# Pinball10.net
KiCad netlist of a schematic drawn in EAGLE
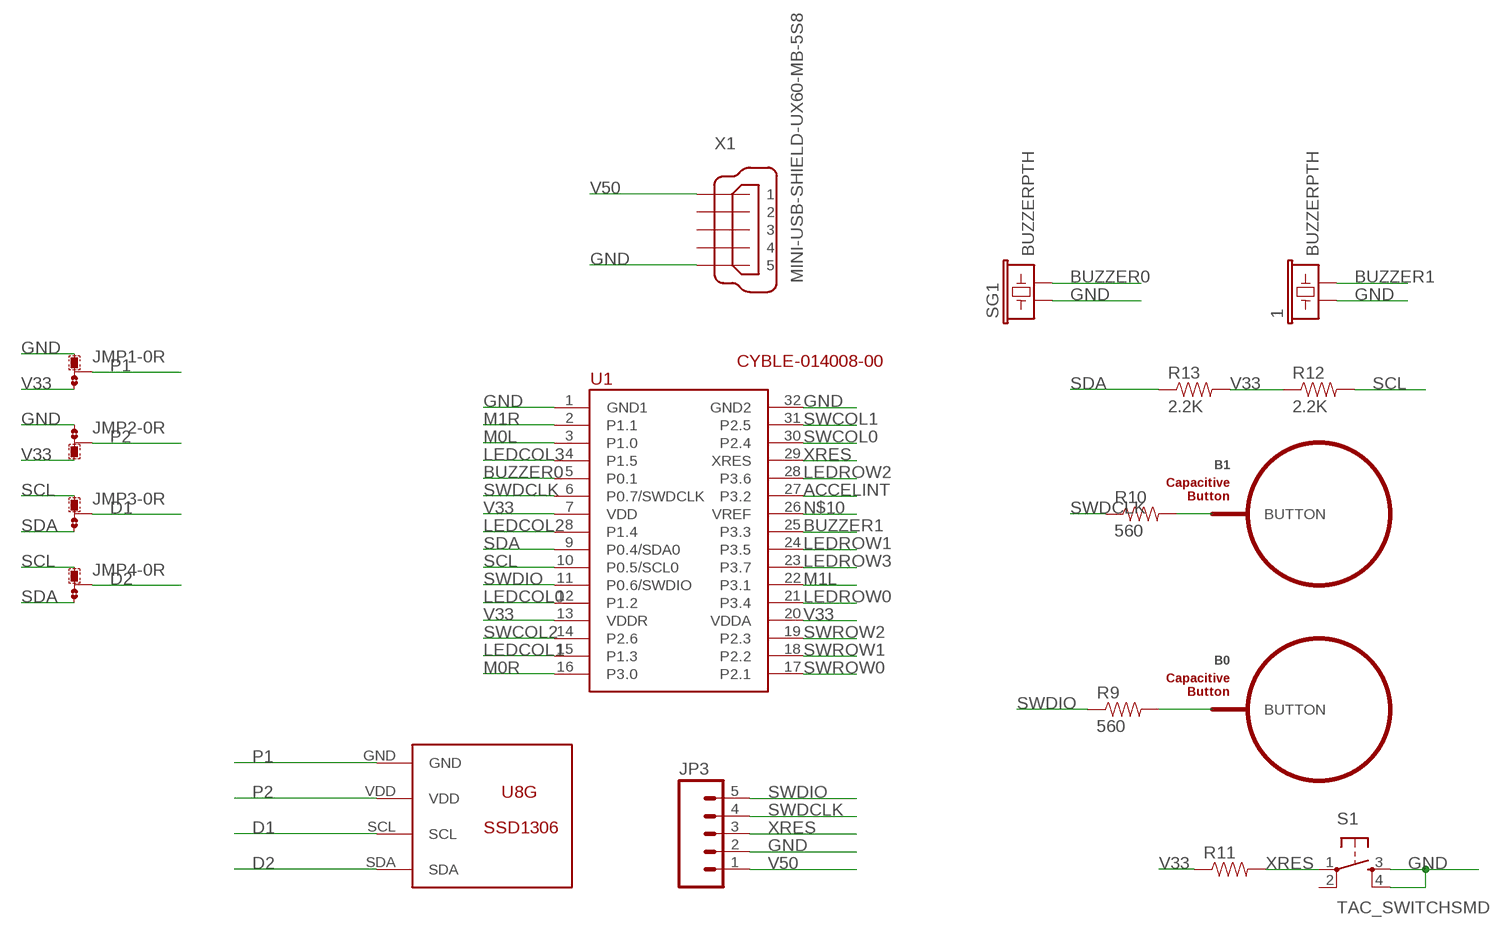
[diagram p0: schematic, sheet 1]
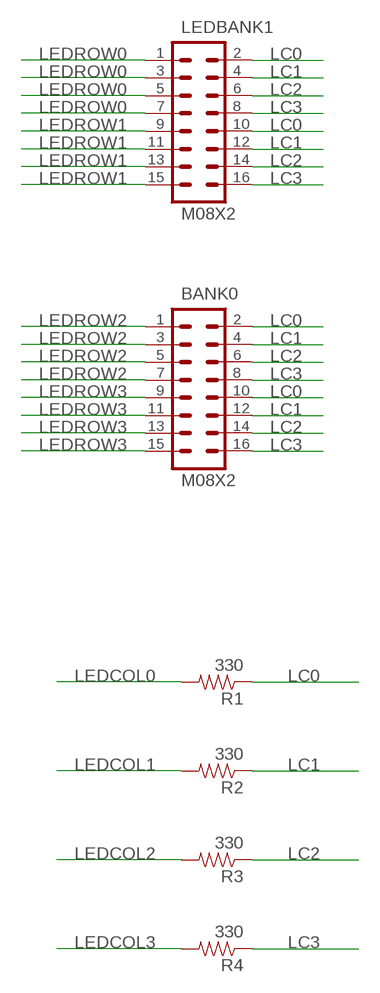
[diagram p1: schematic, sheet 2]
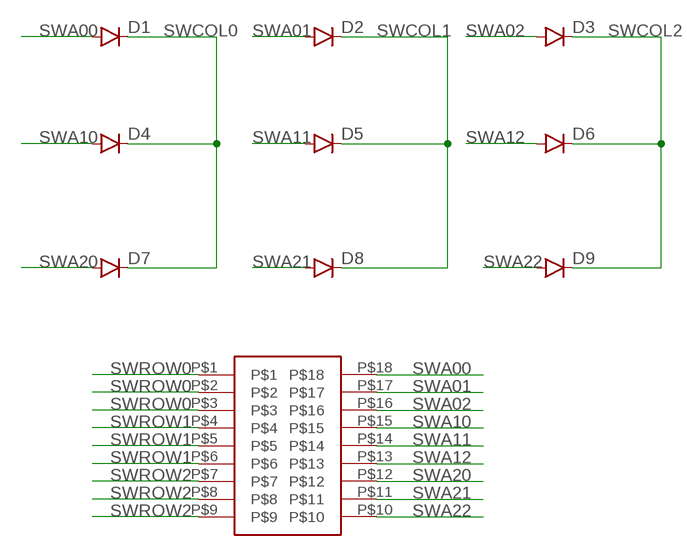
[diagram p2: schematic, sheet 3]
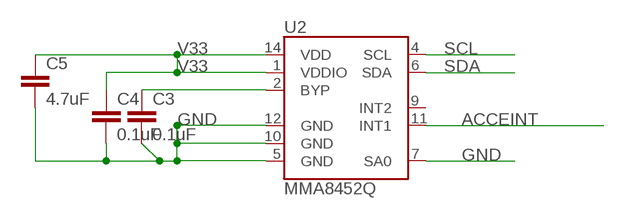
[diagram p3: schematic, sheet 4]
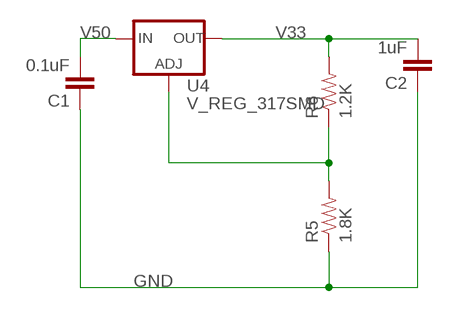
[diagram p4: schematic, sheet 5]
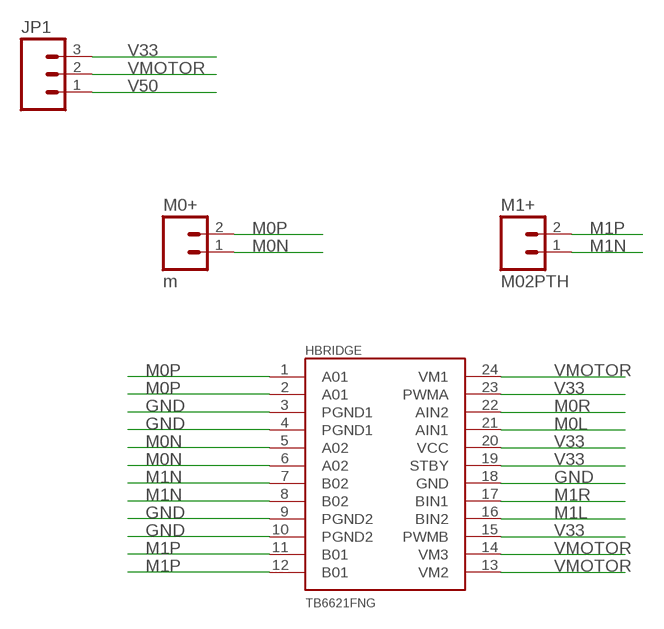
[diagram p5: schematic, sheet 6]
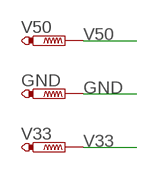
[diagram p6: schematic, sheet 7]

(export (version "E")
  (design (tool "Eeschema 10.0.6"))
  (components
    (comp (ref "GND")
      (value "GND")
      (footprint "eagle-import:P1-13")
      (libsource (lib "eagle-import") (part "PTR1PAD1-13"))
    )
    (comp (ref "V33")
      (value "PTR1PAD1-13")
      (footprint "eagle-import:P1-13")
      (libsource (lib "eagle-import") (part "PTR1PAD1-13"))
    )
    (comp (ref "V50")
      (value "PTR1PAD1-13")
      (footprint "eagle-import:P1-13")
      (libsource (lib "eagle-import") (part "PTR1PAD1-13"))
    )
    (comp (ref "D1")
      (value "DIODESOD")
      (footprint "eagle-import:SOD-323")
      (libsource (lib "eagle-import") (part "DIODESOD"))
    )
    (comp (ref "D2")
      (value "DIODESOD")
      (footprint "eagle-import:SOD-323")
      (libsource (lib "eagle-import") (part "DIODESOD"))
    )
    (comp (ref "D3")
      (value "DIODESOD")
      (footprint "eagle-import:SOD-323")
      (libsource (lib "eagle-import") (part "DIODESOD"))
    )
    (comp (ref "D4")
      (value "DIODESOD")
      (footprint "eagle-import:SOD-323")
      (libsource (lib "eagle-import") (part "DIODESOD"))
    )
    (comp (ref "D5")
      (value "DIODESOD")
      (footprint "eagle-import:SOD-323")
      (libsource (lib "eagle-import") (part "DIODESOD"))
    )
    (comp (ref "D6")
      (value "DIODESOD")
      (footprint "eagle-import:SOD-323")
      (libsource (lib "eagle-import") (part "DIODESOD"))
    )
    (comp (ref "D7")
      (value "DIODESOD")
      (footprint "eagle-import:SOD-323")
      (libsource (lib "eagle-import") (part "DIODESOD"))
    )
    (comp (ref "D8")
      (value "DIODESOD")
      (footprint "eagle-import:SOD-323")
      (libsource (lib "eagle-import") (part "DIODESOD"))
    )
    (comp (ref "D9")
      (value "DIODESOD")
      (footprint "eagle-import:SOD-323")
      (libsource (lib "eagle-import") (part "DIODESOD"))
    )
    (comp (ref "U$1")
      (value "9X2")
      (footprint "eagle-import:9X2")
      (libsource (lib "eagle-import") (part "9X2"))
    )
    (comp (ref "1")
      (value "BUZZERPTH")
      (footprint "eagle-import:BUZZER-12MM")
      (libsource (lib "eagle-import") (part "BUZZERPTH"))
    )
    (comp (ref "B0")
      (value "BUTTON_PASSIVE12MM")
      (footprint "eagle-import:BUTTON_PASSIVE_12MM")
      (libsource (lib "eagle-import") (part "BUTTON_PASSIVE12MM"))
    )
    (comp (ref "B1")
      (value "BUTTON_PASSIVE12MM")
      (footprint "eagle-import:BUTTON_PASSIVE_12MM")
      (libsource (lib "eagle-import") (part "BUTTON_PASSIVE12MM"))
    )
    (comp (ref "JMP1")
      (value "0R-JUMPB")
      (footprint "eagle-import:B0R-JMP")
      (libsource (lib "eagle-import") (part "0R-JUMPB"))
    )
    (comp (ref "JMP2")
      (value "0R-JUMPB")
      (footprint "eagle-import:B0R-JMP")
      (libsource (lib "eagle-import") (part "0R-JUMPB"))
    )
    (comp (ref "JMP3")
      (value "0R-JUMPB")
      (footprint "eagle-import:B0R-JMP")
      (libsource (lib "eagle-import") (part "0R-JUMPB"))
    )
    (comp (ref "JMP4")
      (value "0R-JUMPB")
      (footprint "eagle-import:B0R-JMP")
      (libsource (lib "eagle-import") (part "0R-JUMPB"))
    )
    (comp (ref "JP3")
      (value "M05LOCK")
      (footprint "eagle-import:1X05_LOCK")
      (libsource (lib "eagle-import") (part "M05LOCK"))
    )
    (comp (ref "R9")
      (value "560")
      (footprint "eagle-import:0805")
      (libsource (lib "eagle-import") (part "RESISTOR0805-RES"))
    )
    (comp (ref "R10")
      (value "560")
      (footprint "eagle-import:0805")
      (libsource (lib "eagle-import") (part "RESISTOR0805-RES"))
    )
    (comp (ref "R11")
      (value "RESISTOR0805-RES")
      (footprint "eagle-import:0805")
      (libsource (lib "eagle-import") (part "SparkFun-Resistors_RESISTOR0805-RES"))
    )
    (comp (ref "R12")
      (value "2.2K")
      (footprint "eagle-import:0805")
      (libsource (lib "eagle-import") (part "RESISTOR0805-RES"))
    )
    (comp (ref "R13")
      (value "2.2K")
      (footprint "eagle-import:0805")
      (libsource (lib "eagle-import") (part "RESISTOR0805-RES"))
    )
    (comp (ref "S1")
      (value "TAC_SWITCHSMD")
      (footprint "eagle-import:TACTILE-SWITCH-SMD")
      (libsource (lib "eagle-import") (part "TAC_SWITCHSMD"))
    )
    (comp (ref "SG1")
      (value "BUZZERPTH")
      (footprint "eagle-import:BUZZER-12MM")
      (libsource (lib "eagle-import") (part "BUZZERPTH"))
    )
    (comp (ref "U$2")
      (value "U8G-096-OLED")
      (footprint "eagle-import:096-SSD1306")
      (libsource (lib "eagle-import") (part "U8G-096-OLED"))
    )
    (comp (ref "U1")
      (value "CYBLE-014008-00")
      (footprint "eagle-import:PSOC-BLE-11MM-32")
      (libsource (lib "eagle-import") (part "CYBLE-014008-00"))
    )
    (comp (ref "X1")
      (value "MINI-USB-SHIELD-UX60-MB-5S8")
      (footprint "eagle-import:UX60-MB-5S8")
      (libsource (lib "eagle-import") (part "MINI-USB-SHIELD-UX60-MB-5S8"))
    )
    (comp (ref "C3")
      (value "0.1uF")
      (footprint "eagle-import:0805")
      (libsource (lib "eagle-import") (part "CAP0805"))
    )
    (comp (ref "C4")
      (value "0.1uF")
      (footprint "eagle-import:0805")
      (libsource (lib "eagle-import") (part "CAP0805"))
    )
    (comp (ref "C5")
      (value "4.7uF")
      (footprint "eagle-import:0805")
      (libsource (lib "eagle-import") (part "CAP0805"))
    )
    (comp (ref "U2")
      (value "MMA8452Q")
      (footprint "eagle-import:QFN-16_0.5MM")
      (libsource (lib "eagle-import") (part "MMA8452Q"))
    )
    (comp (ref "C1")
      (value "0.1uF")
      (footprint "eagle-import:0805")
      (libsource (lib "eagle-import") (part "CAP0805"))
    )
    (comp (ref "C2")
      (value "1uF")
      (footprint "eagle-import:0805")
      (libsource (lib "eagle-import") (part "CAP0805"))
    )
    (comp (ref "R5")
      (value "1.8K")
      (footprint "eagle-import:0805")
      (libsource (lib "eagle-import") (part "RESISTOR0805-RES"))
    )
    (comp (ref "R6")
      (value "1.2K")
      (footprint "eagle-import:0805")
      (libsource (lib "eagle-import") (part "RESISTOR0805-RES"))
    )
    (comp (ref "U4")
      (value "V_REG_317SMD")
      (footprint "eagle-import:SOT223")
      (libsource (lib "eagle-import") (part "V_REG_317SMD"))
    )
    (comp (ref "BANK0")
      (value "M08X2")
      (footprint "eagle-import:2X8")
      (libsource (lib "eagle-import") (part "M08X2"))
    )
    (comp (ref "LEDBANK1")
      (value "M08X2")
      (footprint "eagle-import:2X8")
      (libsource (lib "eagle-import") (part "M08X2"))
    )
    (comp (ref "R1")
      (value "330")
      (footprint "eagle-import:0805")
      (libsource (lib "eagle-import") (part "RESISTOR"))
    )
    (comp (ref "R2")
      (value "330")
      (footprint "eagle-import:0805")
      (libsource (lib "eagle-import") (part "RESISTOR"))
    )
    (comp (ref "R3")
      (value "330")
      (footprint "eagle-import:0805")
      (libsource (lib "eagle-import") (part "RESISTOR"))
    )
    (comp (ref "R4")
      (value "330")
      (footprint "eagle-import:0805")
      (libsource (lib "eagle-import") (part "RESISTOR"))
    )
    (comp (ref "HBRIDGE")
      (value "TB6621FNG")
      (footprint "eagle-import:SSOP24")
      (libsource (lib "eagle-import") (part "TB6621FNG"))
    )
    (comp (ref "JP1")
      (value "M03PTH")
      (footprint "eagle-import:1X03")
      (libsource (lib "eagle-import") (part "M03PTH"))
    )
    (comp (ref "M0+")
      (value "m")
      (footprint "eagle-import:1X02")
      (libsource (lib "eagle-import") (part "M02PTH"))
    )
    (comp (ref "M1+")
      (value "M02PTH")
      (footprint "eagle-import:1X02")
      (libsource (lib "eagle-import") (part "M02PTH"))
    )
  )
  (nets
    (net (code "1") (name "ACCEINT") (class "Default")
      (node (ref "U2") (pin "11") (pinfunction "INT1_11") (pintype "bidirectional"))
    )
    (net (code "2") (name "ACCELINT") (class "Default")
      (node (ref "U1") (pin "27") (pinfunction "P3.2_27") (pintype "bidirectional"))
    )
    (net (code "3") (name "BUZZER0") (class "Default")
      (node (ref "SG1") (pin "-") (pinfunction "2_-") (pintype "passive"))
      (node (ref "U1") (pin "5") (pinfunction "P0.1_5") (pintype "bidirectional"))
    )
    (net (code "4") (name "BUZZER1") (class "Default")
      (node (ref "1") (pin "-") (pinfunction "2_-") (pintype "passive"))
      (node (ref "U1") (pin "25") (pinfunction "P3.3_25") (pintype "bidirectional"))
    )
    (net (code "5") (name "D1") (class "Default")
      (node (ref "JMP3") (pin "2") (pinfunction "2_2") (pintype "passive"))
      (node (ref "U$2") (pin "SCL") (pinfunction "SCL_SCL") (pintype "bidirectional"))
    )
    (net (code "6") (name "D2") (class "Default")
      (node (ref "JMP4") (pin "2") (pinfunction "2_2") (pintype "passive"))
      (node (ref "U$2") (pin "SDA") (pinfunction "SDA_SDA") (pintype "bidirectional"))
    )
    (net (code "7") (name "GND") (class "Default")
      (node (ref "1") (pin "+") (pinfunction "1_+") (pintype "passive"))
      (node (ref "C1") (pin "1") (pinfunction "1_1") (pintype "passive"))
      (node (ref "C2") (pin "1") (pinfunction "1_1") (pintype "passive"))
      (node (ref "C3") (pin "2") (pinfunction "2_2") (pintype "passive"))
      (node (ref "C4") (pin "2") (pinfunction "2_2") (pintype "passive"))
      (node (ref "C5") (pin "2") (pinfunction "2_2") (pintype "passive"))
      (node (ref "GND") (pin "TP") (pinfunction "TP_TP") (pintype "input"))
      (node (ref "HBRIDGE") (pin "10") (pinfunction "PGND2_10") (pintype "bidirectional"))
      (node (ref "HBRIDGE") (pin "18") (pinfunction "GND_18") (pintype "bidirectional"))
      (node (ref "HBRIDGE") (pin "3") (pinfunction "PGND1_3") (pintype "bidirectional"))
      (node (ref "HBRIDGE") (pin "4") (pinfunction "PGND1_4") (pintype "bidirectional"))
      (node (ref "HBRIDGE") (pin "9") (pinfunction "PGND2_9") (pintype "bidirectional"))
      (node (ref "JMP1") (pin "1") (pinfunction "1_1") (pintype "passive"))
      (node (ref "JMP2") (pin "1") (pinfunction "1_1") (pintype "passive"))
      (node (ref "JP3") (pin "2") (pinfunction "2_2") (pintype "passive"))
      (node (ref "R5") (pin "1") (pinfunction "1_1") (pintype "passive"))
      (node (ref "S1") (pin "3") (pinfunction "3_3") (pintype "passive"))
      (node (ref "S1") (pin "4") (pinfunction "4_4") (pintype "passive"))
      (node (ref "SG1") (pin "+") (pinfunction "1_+") (pintype "passive"))
      (node (ref "U1") (pin "1") (pinfunction "GND1_1") (pintype "power_in"))
      (node (ref "U1") (pin "32") (pinfunction "GND2_32") (pintype "power_in"))
      (node (ref "U2") (pin "10") (pinfunction "GND_10") (pintype "bidirectional"))
      (node (ref "U2") (pin "12") (pinfunction "GND_12") (pintype "bidirectional"))
      (node (ref "U2") (pin "5") (pinfunction "GND_5") (pintype "bidirectional"))
      (node (ref "U2") (pin "7") (pinfunction "SA0_7") (pintype "bidirectional"))
      (node (ref "X1") (pin "5") (pinfunction "5_5") (pintype "input"))
    )
    (net (code "8") (name "LC0") (class "Default")
      (node (ref "BANK0") (pin "10") (pinfunction "10_10") (pintype "passive"))
      (node (ref "BANK0") (pin "2") (pinfunction "2_2") (pintype "passive"))
      (node (ref "LEDBANK1") (pin "10") (pinfunction "10_10") (pintype "passive"))
      (node (ref "LEDBANK1") (pin "2") (pinfunction "2_2") (pintype "passive"))
      (node (ref "R1") (pin "1") (pinfunction "1_1") (pintype "passive"))
    )
    (net (code "9") (name "LC1") (class "Default")
      (node (ref "BANK0") (pin "12") (pinfunction "12_12") (pintype "passive"))
      (node (ref "BANK0") (pin "4") (pinfunction "4_4") (pintype "passive"))
      (node (ref "LEDBANK1") (pin "12") (pinfunction "12_12") (pintype "passive"))
      (node (ref "LEDBANK1") (pin "4") (pinfunction "4_4") (pintype "passive"))
      (node (ref "R2") (pin "1") (pinfunction "1_1") (pintype "passive"))
    )
    (net (code "10") (name "LC2") (class "Default")
      (node (ref "BANK0") (pin "14") (pinfunction "14_14") (pintype "passive"))
      (node (ref "BANK0") (pin "6") (pinfunction "6_6") (pintype "passive"))
      (node (ref "LEDBANK1") (pin "14") (pinfunction "14_14") (pintype "passive"))
      (node (ref "LEDBANK1") (pin "6") (pinfunction "6_6") (pintype "passive"))
      (node (ref "R3") (pin "1") (pinfunction "1_1") (pintype "passive"))
    )
    (net (code "11") (name "LC3") (class "Default")
      (node (ref "BANK0") (pin "16") (pinfunction "16_16") (pintype "passive"))
      (node (ref "BANK0") (pin "8") (pinfunction "8_8") (pintype "passive"))
      (node (ref "LEDBANK1") (pin "16") (pinfunction "16_16") (pintype "passive"))
      (node (ref "LEDBANK1") (pin "8") (pinfunction "8_8") (pintype "passive"))
      (node (ref "R4") (pin "1") (pinfunction "1_1") (pintype "passive"))
    )
    (net (code "12") (name "LEDCOL0") (class "Default")
      (node (ref "R1") (pin "2") (pinfunction "2_2") (pintype "passive"))
      (node (ref "U1") (pin "12") (pinfunction "P1.2_12") (pintype "bidirectional"))
    )
    (net (code "13") (name "LEDCOL1") (class "Default")
      (node (ref "R2") (pin "2") (pinfunction "2_2") (pintype "passive"))
      (node (ref "U1") (pin "15") (pinfunction "P1.3_15") (pintype "bidirectional"))
    )
    (net (code "14") (name "LEDCOL2") (class "Default")
      (node (ref "R3") (pin "2") (pinfunction "2_2") (pintype "passive"))
      (node (ref "U1") (pin "8") (pinfunction "P1.4_8") (pintype "bidirectional"))
    )
    (net (code "15") (name "LEDCOL3") (class "Default")
      (node (ref "R4") (pin "2") (pinfunction "2_2") (pintype "passive"))
      (node (ref "U1") (pin "4") (pinfunction "P1.5_4") (pintype "bidirectional"))
    )
    (net (code "16") (name "LEDROW0") (class "Default")
      (node (ref "LEDBANK1") (pin "1") (pinfunction "1_1") (pintype "passive"))
      (node (ref "LEDBANK1") (pin "3") (pinfunction "3_3") (pintype "passive"))
      (node (ref "LEDBANK1") (pin "5") (pinfunction "5_5") (pintype "passive"))
      (node (ref "LEDBANK1") (pin "7") (pinfunction "7_7") (pintype "passive"))
      (node (ref "U1") (pin "21") (pinfunction "P3.4_21") (pintype "bidirectional"))
    )
    (net (code "17") (name "LEDROW1") (class "Default")
      (node (ref "LEDBANK1") (pin "11") (pinfunction "11_11") (pintype "passive"))
      (node (ref "LEDBANK1") (pin "13") (pinfunction "13_13") (pintype "passive"))
      (node (ref "LEDBANK1") (pin "15") (pinfunction "15_15") (pintype "passive"))
      (node (ref "LEDBANK1") (pin "9") (pinfunction "9_9") (pintype "passive"))
      (node (ref "U1") (pin "24") (pinfunction "P3.5_24") (pintype "bidirectional"))
    )
    (net (code "18") (name "LEDROW2") (class "Default")
      (node (ref "BANK0") (pin "1") (pinfunction "1_1") (pintype "passive"))
      (node (ref "BANK0") (pin "3") (pinfunction "3_3") (pintype "passive"))
      (node (ref "BANK0") (pin "5") (pinfunction "5_5") (pintype "passive"))
      (node (ref "BANK0") (pin "7") (pinfunction "7_7") (pintype "passive"))
      (node (ref "U1") (pin "28") (pinfunction "P3.6_28") (pintype "bidirectional"))
    )
    (net (code "19") (name "LEDROW3") (class "Default")
      (node (ref "BANK0") (pin "11") (pinfunction "11_11") (pintype "passive"))
      (node (ref "BANK0") (pin "13") (pinfunction "13_13") (pintype "passive"))
      (node (ref "BANK0") (pin "15") (pinfunction "15_15") (pintype "passive"))
      (node (ref "BANK0") (pin "9") (pinfunction "9_9") (pintype "passive"))
      (node (ref "U1") (pin "23") (pinfunction "P3.7_23") (pintype "bidirectional"))
    )
    (net (code "20") (name "M0L") (class "Default")
      (node (ref "HBRIDGE") (pin "21") (pinfunction "AIN1_21") (pintype "bidirectional"))
      (node (ref "U1") (pin "3") (pinfunction "P1.0_3") (pintype "bidirectional"))
    )
    (net (code "21") (name "M0N") (class "Default")
      (node (ref "HBRIDGE") (pin "5") (pinfunction "A02_5") (pintype "bidirectional"))
      (node (ref "HBRIDGE") (pin "6") (pinfunction "A02_6") (pintype "bidirectional"))
      (node (ref "M0+") (pin "1") (pinfunction "1_1") (pintype "passive"))
    )
    (net (code "22") (name "M0P") (class "Default")
      (node (ref "HBRIDGE") (pin "1") (pinfunction "A01_1") (pintype "bidirectional"))
      (node (ref "HBRIDGE") (pin "2") (pinfunction "A01_2") (pintype "bidirectional"))
      (node (ref "M0+") (pin "2") (pinfunction "2_2") (pintype "passive"))
    )
    (net (code "23") (name "M0R") (class "Default")
      (node (ref "HBRIDGE") (pin "22") (pinfunction "AIN2_22") (pintype "bidirectional"))
      (node (ref "U1") (pin "16") (pinfunction "P3.0_16") (pintype "bidirectional"))
    )
    (net (code "24") (name "M1L") (class "Default")
      (node (ref "HBRIDGE") (pin "16") (pinfunction "BIN2_16") (pintype "bidirectional"))
      (node (ref "U1") (pin "22") (pinfunction "P3.1_22") (pintype "bidirectional"))
    )
    (net (code "25") (name "M1N") (class "Default")
      (node (ref "HBRIDGE") (pin "7") (pinfunction "B02_7") (pintype "bidirectional"))
      (node (ref "HBRIDGE") (pin "8") (pinfunction "B02_8") (pintype "bidirectional"))
      (node (ref "M1+") (pin "1") (pinfunction "1_1") (pintype "passive"))
    )
    (net (code "26") (name "M1P") (class "Default")
      (node (ref "HBRIDGE") (pin "11") (pinfunction "B01_11") (pintype "bidirectional"))
      (node (ref "HBRIDGE") (pin "12") (pinfunction "B01_12") (pintype "bidirectional"))
      (node (ref "M1+") (pin "2") (pinfunction "2_2") (pintype "passive"))
    )
    (net (code "27") (name "M1R") (class "Default")
      (node (ref "HBRIDGE") (pin "17") (pinfunction "BIN1_17") (pintype "bidirectional"))
      (node (ref "U1") (pin "2") (pinfunction "P1.1_2") (pintype "bidirectional"))
    )
    (net (code "28") (name "N$10") (class "Default")
      (node (ref "U1") (pin "26") (pinfunction "VREF_26") (pintype "input"))
    )
    (net (code "29") (name "Net-(B0-PadBUTTON)") (class "Default")
      (node (ref "B0") (pin "BUTTON") (pinfunction "BUTTON_BUTTON") (pintype "passive"))
      (node (ref "R9") (pin "2") (pinfunction "2_2") (pintype "passive"))
    )
    (net (code "30") (name "Net-(B1-PadBUTTON)") (class "Default")
      (node (ref "B1") (pin "BUTTON") (pinfunction "BUTTON_BUTTON") (pintype "passive"))
      (node (ref "R10") (pin "2") (pinfunction "2_2") (pintype "passive"))
    )
    (net (code "31") (name "Net-(U2-BYP)") (class "Default")
      (node (ref "C3") (pin "1") (pinfunction "1_1") (pintype "passive"))
      (node (ref "U2") (pin "2") (pinfunction "BYP_2") (pintype "bidirectional"))
    )
    (net (code "32") (name "Net-(U4-ADJ)") (class "Default")
      (node (ref "R5") (pin "2") (pinfunction "2_2") (pintype "passive"))
      (node (ref "R6") (pin "1") (pinfunction "1_1") (pintype "passive"))
      (node (ref "U4") (pin "1") (pinfunction "ADJ_1") (pintype "input"))
    )
    (net (code "33") (name "P1") (class "Default")
      (node (ref "JMP1") (pin "2") (pinfunction "2_2") (pintype "passive"))
      (node (ref "U$2") (pin "GND") (pinfunction "GND_GND") (pintype "power_in"))
    )
    (net (code "34") (name "P2") (class "Default")
      (node (ref "JMP2") (pin "2") (pinfunction "2_2") (pintype "passive"))
      (node (ref "U$2") (pin "VDD") (pinfunction "VDD_VDD") (pintype "power_in"))
    )
    (net (code "35") (name "SCL") (class "Default")
      (node (ref "JMP3") (pin "1") (pinfunction "1_1") (pintype "passive"))
      (node (ref "JMP4") (pin "1") (pinfunction "1_1") (pintype "passive"))
      (node (ref "R12") (pin "2") (pinfunction "2_2") (pintype "passive"))
      (node (ref "U1") (pin "10") (pinfunction "P0.5/SCL0_10") (pintype "bidirectional"))
      (node (ref "U2") (pin "4") (pinfunction "SCL_4") (pintype "bidirectional"))
    )
    (net (code "36") (name "SDA") (class "Default")
      (node (ref "JMP3") (pin "3") (pinfunction "3_3") (pintype "passive"))
      (node (ref "JMP4") (pin "3") (pinfunction "3_3") (pintype "passive"))
      (node (ref "R13") (pin "1") (pinfunction "1_1") (pintype "passive"))
      (node (ref "U1") (pin "9") (pinfunction "P0.4/SDA0_9") (pintype "bidirectional"))
      (node (ref "U2") (pin "6") (pinfunction "SDA_6") (pintype "bidirectional"))
    )
    (net (code "37") (name "SWA00") (class "Default")
      (node (ref "D1") (pin "A") (pinfunction "A_A") (pintype "passive"))
      (node (ref "U$1") (pin "P$18") (pinfunction "P$18_P$18") (pintype "bidirectional"))
    )
    (net (code "38") (name "SWA01") (class "Default")
      (node (ref "D2") (pin "A") (pinfunction "A_A") (pintype "passive"))
      (node (ref "U$1") (pin "P$17") (pinfunction "P$17_P$17") (pintype "bidirectional"))
    )
    (net (code "39") (name "SWA02") (class "Default")
      (node (ref "D3") (pin "A") (pinfunction "A_A") (pintype "passive"))
      (node (ref "U$1") (pin "P$16") (pinfunction "P$16_P$16") (pintype "bidirectional"))
    )
    (net (code "40") (name "SWA10") (class "Default")
      (node (ref "D4") (pin "A") (pinfunction "A_A") (pintype "passive"))
      (node (ref "U$1") (pin "P$15") (pinfunction "P$15_P$15") (pintype "bidirectional"))
    )
    (net (code "41") (name "SWA11") (class "Default")
      (node (ref "D5") (pin "A") (pinfunction "A_A") (pintype "passive"))
      (node (ref "U$1") (pin "P$14") (pinfunction "P$14_P$14") (pintype "bidirectional"))
    )
    (net (code "42") (name "SWA12") (class "Default")
      (node (ref "D6") (pin "A") (pinfunction "A_A") (pintype "passive"))
      (node (ref "U$1") (pin "P$13") (pinfunction "P$13_P$13") (pintype "bidirectional"))
    )
    (net (code "43") (name "SWA20") (class "Default")
      (node (ref "D7") (pin "A") (pinfunction "A_A") (pintype "passive"))
      (node (ref "U$1") (pin "P$12") (pinfunction "P$12_P$12") (pintype "bidirectional"))
    )
    (net (code "44") (name "SWA21") (class "Default")
      (node (ref "D8") (pin "A") (pinfunction "A_A") (pintype "passive"))
      (node (ref "U$1") (pin "P$11") (pinfunction "P$11_P$11") (pintype "bidirectional"))
    )
    (net (code "45") (name "SWA22") (class "Default")
      (node (ref "D9") (pin "A") (pinfunction "A_A") (pintype "passive"))
      (node (ref "U$1") (pin "P$10") (pinfunction "P$10_P$10") (pintype "bidirectional"))
    )
    (net (code "46") (name "SWCOL0") (class "Default")
      (node (ref "D1") (pin "C") (pinfunction "C_C") (pintype "passive"))
      (node (ref "D4") (pin "C") (pinfunction "C_C") (pintype "passive"))
      (node (ref "D7") (pin "C") (pinfunction "C_C") (pintype "passive"))
      (node (ref "U1") (pin "30") (pinfunction "P2.4_30") (pintype "bidirectional"))
    )
    (net (code "47") (name "SWCOL1") (class "Default")
      (node (ref "D2") (pin "C") (pinfunction "C_C") (pintype "passive"))
      (node (ref "D5") (pin "C") (pinfunction "C_C") (pintype "passive"))
      (node (ref "D8") (pin "C") (pinfunction "C_C") (pintype "passive"))
      (node (ref "U1") (pin "31") (pinfunction "P2.5_31") (pintype "bidirectional"))
    )
    (net (code "48") (name "SWCOL2") (class "Default")
      (node (ref "D3") (pin "C") (pinfunction "C_C") (pintype "passive"))
      (node (ref "D6") (pin "C") (pinfunction "C_C") (pintype "passive"))
      (node (ref "D9") (pin "C") (pinfunction "C_C") (pintype "passive"))
      (node (ref "U1") (pin "14") (pinfunction "P2.6_14") (pintype "bidirectional"))
    )
    (net (code "49") (name "SWDCLK") (class "Default")
      (node (ref "JP3") (pin "4") (pinfunction "4_4") (pintype "passive"))
      (node (ref "R10") (pin "1") (pinfunction "1_1") (pintype "passive"))
      (node (ref "U1") (pin "6") (pinfunction "P0.7/SWDCLK_6") (pintype "bidirectional"))
    )
    (net (code "50") (name "SWDIO") (class "Default")
      (node (ref "JP3") (pin "5") (pinfunction "5_5") (pintype "passive"))
      (node (ref "R9") (pin "1") (pinfunction "1_1") (pintype "passive"))
      (node (ref "U1") (pin "11") (pinfunction "P0.6/SWDIO_11") (pintype "bidirectional"))
    )
    (net (code "51") (name "SWROW0") (class "Default")
      (node (ref "U$1") (pin "P$1") (pinfunction "P$1_P$1") (pintype "bidirectional"))
      (node (ref "U$1") (pin "P$2") (pinfunction "P$2_P$2") (pintype "bidirectional"))
      (node (ref "U$1") (pin "P$3") (pinfunction "P$3_P$3") (pintype "bidirectional"))
      (node (ref "U1") (pin "17") (pinfunction "P2.1_17") (pintype "bidirectional"))
    )
    (net (code "52") (name "SWROW1") (class "Default")
      (node (ref "U$1") (pin "P$4") (pinfunction "P$4_P$4") (pintype "bidirectional"))
      (node (ref "U$1") (pin "P$5") (pinfunction "P$5_P$5") (pintype "bidirectional"))
      (node (ref "U$1") (pin "P$6") (pinfunction "P$6_P$6") (pintype "bidirectional"))
      (node (ref "U1") (pin "18") (pinfunction "P2.2_18") (pintype "bidirectional"))
    )
    (net (code "53") (name "SWROW2") (class "Default")
      (node (ref "U$1") (pin "P$7") (pinfunction "P$7_P$7") (pintype "bidirectional"))
      (node (ref "U$1") (pin "P$8") (pinfunction "P$8_P$8") (pintype "bidirectional"))
      (node (ref "U$1") (pin "P$9") (pinfunction "P$9_P$9") (pintype "bidirectional"))
      (node (ref "U1") (pin "19") (pinfunction "P2.3_19") (pintype "bidirectional"))
    )
    (net (code "54") (name "V33") (class "Default")
      (node (ref "C2") (pin "2") (pinfunction "2_2") (pintype "passive"))
      (node (ref "C4") (pin "1") (pinfunction "1_1") (pintype "passive"))
      (node (ref "C5") (pin "1") (pinfunction "1_1") (pintype "passive"))
      (node (ref "HBRIDGE") (pin "15") (pinfunction "PWMB_15") (pintype "bidirectional"))
      (node (ref "HBRIDGE") (pin "19") (pinfunction "STBY_19") (pintype "bidirectional"))
      (node (ref "HBRIDGE") (pin "20") (pinfunction "VCC_20") (pintype "bidirectional"))
      (node (ref "HBRIDGE") (pin "23") (pinfunction "PWMA_23") (pintype "bidirectional"))
      (node (ref "JMP1") (pin "3") (pinfunction "3_3") (pintype "passive"))
      (node (ref "JMP2") (pin "3") (pinfunction "3_3") (pintype "passive"))
      (node (ref "JP1") (pin "3") (pinfunction "3_3") (pintype "passive"))
      (node (ref "R11") (pin "1") (pinfunction "1_1") (pintype "passive"))
      (node (ref "R12") (pin "1") (pinfunction "1_1") (pintype "passive"))
      (node (ref "R13") (pin "2") (pinfunction "2_2") (pintype "passive"))
      (node (ref "R6") (pin "2") (pinfunction "2_2") (pintype "passive"))
      (node (ref "U1") (pin "13") (pinfunction "VDDR_13") (pintype "power_in"))
      (node (ref "U1") (pin "20") (pinfunction "VDDA_20") (pintype "power_in"))
      (node (ref "U1") (pin "7") (pinfunction "VDD_7") (pintype "power_in"))
      (node (ref "U2") (pin "1") (pinfunction "VDDIO_1") (pintype "bidirectional"))
      (node (ref "U2") (pin "14") (pinfunction "VDD_14") (pintype "bidirectional"))
      (node (ref "U4") (pin "2") (pinfunction "OUT_2") (pintype "output"))
      (node (ref "V33") (pin "TP") (pinfunction "TP_TP") (pintype "input"))
    )
    (net (code "55") (name "V50") (class "Default")
      (node (ref "C1") (pin "2") (pinfunction "2_2") (pintype "passive"))
      (node (ref "JP1") (pin "1") (pinfunction "1_1") (pintype "passive"))
      (node (ref "JP3") (pin "1") (pinfunction "1_1") (pintype "passive"))
      (node (ref "U4") (pin "3") (pinfunction "IN_3") (pintype "input"))
      (node (ref "V50") (pin "TP") (pinfunction "TP_TP") (pintype "input"))
      (node (ref "X1") (pin "1") (pinfunction "1_1") (pintype "input"))
    )
    (net (code "56") (name "VMOTOR") (class "Default")
      (node (ref "HBRIDGE") (pin "13") (pinfunction "VM2_13") (pintype "bidirectional"))
      (node (ref "HBRIDGE") (pin "14") (pinfunction "VM3_14") (pintype "bidirectional"))
      (node (ref "HBRIDGE") (pin "24") (pinfunction "VM1_24") (pintype "bidirectional"))
      (node (ref "JP1") (pin "2") (pinfunction "2_2") (pintype "passive"))
    )
    (net (code "57") (name "XRES") (class "Default")
      (node (ref "JP3") (pin "3") (pinfunction "3_3") (pintype "passive"))
      (node (ref "R11") (pin "2") (pinfunction "2_2") (pintype "passive"))
      (node (ref "S1") (pin "1") (pinfunction "1_1") (pintype "passive"))
      (node (ref "U1") (pin "29") (pinfunction "XRES_29") (pintype "input"))
    )
    (net (code "58") (name "unconnected-(S1-Pad2)") (class "Default")
      (node (ref "S1") (pin "2") (pinfunction "2_2") (pintype "passive"))
    )
    (net (code "59") (name "unconnected-(U2-INT2-Pad9)") (class "Default")
      (node (ref "U2") (pin "9") (pinfunction "INT2_9") (pintype "bidirectional"))
    )
    (net (code "60") (name "unconnected-(X1-Pad2)") (class "Default")
      (node (ref "X1") (pin "2") (pinfunction "2_2") (pintype "input"))
    )
    (net (code "61") (name "unconnected-(X1-Pad3)") (class "Default")
      (node (ref "X1") (pin "3") (pinfunction "3_3") (pintype "input"))
    )
    (net (code "62") (name "unconnected-(X1-Pad4)") (class "Default")
      (node (ref "X1") (pin "4") (pinfunction "4_4") (pintype "input"))
    )
  )
)
